# LTC6362_Schematic.net
KiCad netlist of a schematic drawn in Altium Designer
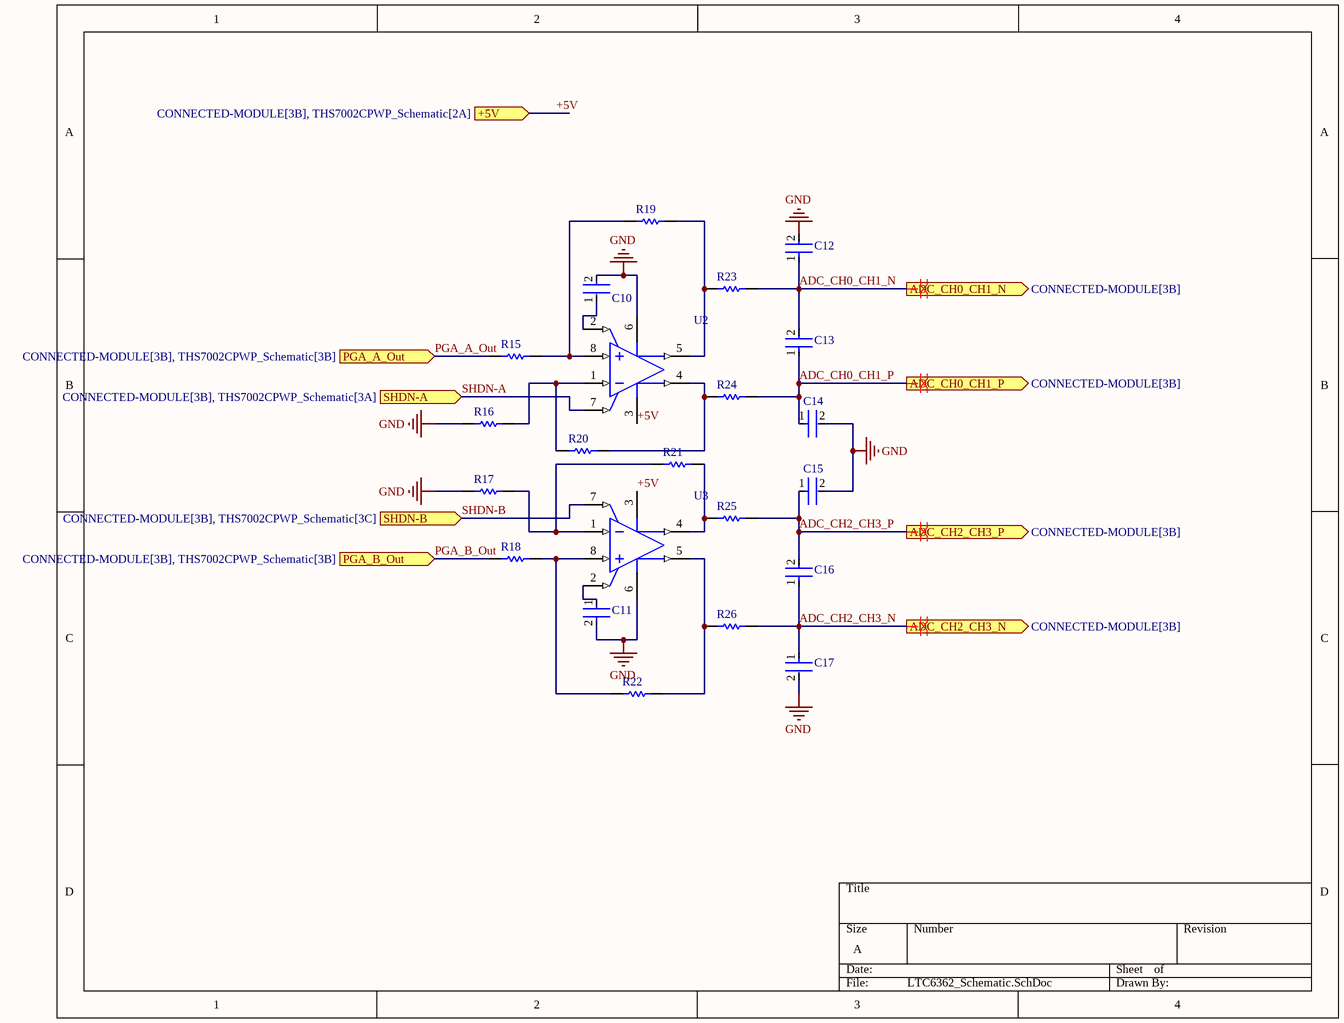
[diagram p0: LTC6362_Schematic.SchDoc]

(export (version "E")
  (design (tool "Eeschema 10.0.6"))
  (components
    (comp (ref "C10")
      (value "GRM155R71C104KA88D")
      (footprint "FP-GRM15-MFG")
      (description "CAP CER 0.1UF 16V X7R 0402")
      (fields
        (field (name "TOLERANCE") "10%")
        (field (name "OCTOPART") "https://octopart.com/grm155r71c104ka88d-murata-196880")
      )
      (libsource (lib "Altium Content Vault") (part "236180d848d6139a670b325ea6854c9"))
    )
    (comp (ref "C11")
      (value "GRM155R71C104KA88D")
      (footprint "FP-GRM15-MFG")
      (description "CAP CER 0.1UF 16V X7R 0402")
      (fields
        (field (name "TOLERANCE") "10%")
        (field (name "OCTOPART") "https://octopart.com/grm155r71c104ka88d-murata-196880")
      )
      (libsource (lib "Altium Content Vault") (part "236180d848d6139a670b325ea6854c9"))
    )
    (comp (ref "C12")
      (value "C0402C392K3RACTU")
      (footprint "FP-C0402-BB-MFG")
      (description "CAP CER 3900PF 25V X7R 0402")
      (fields
        (field (name "MANUFACTURER") "Kemet")
        (field (name "OCTOPART") "https://octopart.com/c0402c392k3ractu-kemet-141288")
      )
      (libsource (lib "Altium Content Vault") (part "b4654b650e69147ec39a6b967a45e02"))
    )
    (comp (ref "C13")
      (value "C0402C392K3RACTU")
      (footprint "FP-C0402-BB-MFG")
      (description "CAP CER 3900PF 25V X7R 0402")
      (fields
        (field (name "MANUFACTURER") "Kemet")
        (field (name "OCTOPART") "https://octopart.com/c0402c392k3ractu-kemet-141288")
      )
      (libsource (lib "Altium Content Vault") (part "b4654b650e69147ec39a6b967a45e02"))
    )
    (comp (ref "C14")
      (value "C0402C392K3RACTU")
      (footprint "FP-C0402-BB-MFG")
      (description "CAP CER 3900PF 25V X7R 0402")
      (fields
        (field (name "MANUFACTURER") "Kemet")
        (field (name "OCTOPART") "https://octopart.com/c0402c392k3ractu-kemet-141288")
      )
      (libsource (lib "Altium Content Vault") (part "b4654b650e69147ec39a6b967a45e02"))
    )
    (comp (ref "C15")
      (value "C0402C392K3RACTU")
      (footprint "FP-C0402-BB-MFG")
      (description "CAP CER 3900PF 25V X7R 0402")
      (fields
        (field (name "MANUFACTURER") "Kemet")
        (field (name "OCTOPART") "https://octopart.com/c0402c392k3ractu-kemet-141288")
      )
      (libsource (lib "Altium Content Vault") (part "b4654b650e69147ec39a6b967a45e02"))
    )
    (comp (ref "C16")
      (value "C0402C392K3RACTU")
      (footprint "FP-C0402-BB-MFG")
      (description "CAP CER 3900PF 25V X7R 0402")
      (fields
        (field (name "MANUFACTURER") "Kemet")
        (field (name "OCTOPART") "https://octopart.com/c0402c392k3ractu-kemet-141288")
      )
      (libsource (lib "Altium Content Vault") (part "b4654b650e69147ec39a6b967a45e02"))
    )
    (comp (ref "C17")
      (value "C0402C392K3RACTU")
      (footprint "FP-C0402-BB-MFG")
      (description "CAP CER 3900PF 25V X7R 0402")
      (fields
        (field (name "MANUFACTURER") "Kemet")
        (field (name "OCTOPART") "https://octopart.com/c0402c392k3ractu-kemet-141288")
      )
      (libsource (lib "Altium Content Vault") (part "b4654b650e69147ec39a6b967a45e02"))
    )
    (comp (ref "R15")
      (value "ERJ-2RKF1241X")
      (footprint "RESC1005X40X25ML05T05")
      (fields (field (name "MANUFACTURER") "Panasonic"))
      (libsource (lib "Altium Content Vault") (part "RES"))
    )
    (comp (ref "R16")
      (value "ERJ-2RKF1241X")
      (footprint "RESC1005X40X25ML05T05")
      (fields (field (name "MANUFACTURER") "Panasonic"))
      (libsource (lib "Altium Content Vault") (part "RES"))
    )
    (comp (ref "R17")
      (value "ERJ-2RKF1241X")
      (footprint "RESC1005X40X25ML05T05")
      (fields (field (name "MANUFACTURER") "Panasonic"))
      (libsource (lib "Altium Content Vault") (part "RES"))
    )
    (comp (ref "R18")
      (value "ERJ-2RKF1241X")
      (footprint "RESC1005X40X25ML05T05")
      (fields (field (name "MANUFACTURER") "Panasonic"))
      (libsource (lib "Altium Content Vault") (part "RES"))
    )
    (comp (ref "R19")
      (value "ERJ-2RKF1001X")
      (footprint "RESC1005X40X25NL05T05")
      (description "Chip Resistor, 1 KOhm, +/- 1%, 100 mW, -55 to 155 degC, 0402 (1005 Metric), RoHS, Tape and Reel")
      (fields (field (name "MANUFACTURER") "Basic Passives") (field (name "TOLERANCE") "1%"))
      (libsource (lib "Altium Content Vault") (part "RES-2"))
    )
    (comp (ref "R20")
      (value "ERJ-2RKF1001X")
      (footprint "RESC1005X40X25NL05T05")
      (description "Chip Resistor, 1 KOhm, +/- 1%, 100 mW, -55 to 155 degC, 0402 (1005 Metric), RoHS, Tape and Reel")
      (fields (field (name "MANUFACTURER") "Basic Passives") (field (name "TOLERANCE") "1%"))
      (libsource (lib "Altium Content Vault") (part "RES-2"))
    )
    (comp (ref "R21")
      (value "ERJ-2RKF1001X")
      (footprint "RESC1005X40X25NL05T05")
      (description "Chip Resistor, 1 KOhm, +/- 1%, 100 mW, -55 to 155 degC, 0402 (1005 Metric), RoHS, Tape and Reel")
      (fields (field (name "MANUFACTURER") "Basic Passives") (field (name "TOLERANCE") "1%"))
      (libsource (lib "Altium Content Vault") (part "RES-2"))
    )
    (comp (ref "R22")
      (value "ERJ-2RKF1001X")
      (footprint "RESC1005X40X25NL05T05")
      (description "Chip Resistor, 1 KOhm, +/- 1%, 100 mW, -55 to 155 degC, 0402 (1005 Metric), RoHS, Tape and Reel")
      (fields (field (name "MANUFACTURER") "Basic Passives") (field (name "TOLERANCE") "1%"))
      (libsource (lib "Altium Content Vault") (part "RES-2"))
    )
    (comp (ref "R23")
      (value "RC0402FR-0735R7L")
      (footprint "RESC1005X40X25ML05T10")
      (fields (field (name "MANUFACTURER") "Yageo"))
      (libsource (lib "Altium Content Vault") (part "RES"))
    )
    (comp (ref "R24")
      (value "RC0402FR-0735R7L")
      (footprint "RESC1005X40X25ML05T10")
      (fields (field (name "MANUFACTURER") "Yageo"))
      (libsource (lib "Altium Content Vault") (part "RES"))
    )
    (comp (ref "R25")
      (value "RC0402FR-0735R7L")
      (footprint "RESC1005X40X25ML05T10")
      (fields (field (name "MANUFACTURER") "Yageo"))
      (libsource (lib "Altium Content Vault") (part "RES"))
    )
    (comp (ref "R26")
      (value "RC0402FR-0735R7L")
      (footprint "RESC1005X40X25ML05T10")
      (fields (field (name "MANUFACTURER") "Yageo"))
      (libsource (lib "Altium Content Vault") (part "RES"))
    )
    (comp (ref "U2")
      (value "LTC6362HMS8#PBF")
      (footprint "LT-MS8-8_L")
      (fields
        (field (name "LINEAR TECHNOLOGY PART NUMBER") "LTC6362")
        (field (name "MANUFACTURER") "Linear Technology")
      )
      (libsource (lib "LTC6362HMS_Schematic") (part "CMP-0359-00920-2"))
    )
    (comp (ref "U3")
      (value "LTC6362HMS8#PBF")
      (footprint "LT-MS8-8_L")
      (fields
        (field (name "LINEAR TECHNOLOGY PART NUMBER") "LTC6362")
        (field (name "MANUFACTURER") "Linear Technology")
      )
      (libsource (lib "LTC6362HMS_Schematic") (part "CMP-0359-00920-2"))
    )
  )
  (nets
    (net (code "1") (name "/+5V") (class "Default")
      (node (ref "U2") (pin "3") (pinfunction "V+_3") (pintype "power_in"))
      (node (ref "U3") (pin "3") (pinfunction "V+_3") (pintype "power_in"))
    )
    (net (code "2") (name "/ADC_CH0_CH1_N") (class "Default")
      (node (ref "C12") (pin "1") (pinfunction "1_1") (pintype "passive"))
      (node (ref "C13") (pin "2") (pinfunction "2_2") (pintype "passive"))
      (node (ref "R23") (pin "2") (pinfunction "2_2") (pintype "passive"))
    )
    (net (code "3") (name "/ADC_CH0_CH1_P") (class "Default")
      (node (ref "C13") (pin "1") (pinfunction "1_1") (pintype "passive"))
      (node (ref "C14") (pin "1") (pinfunction "1_1") (pintype "passive"))
      (node (ref "R24") (pin "2") (pinfunction "2_2") (pintype "passive"))
    )
    (net (code "4") (name "/ADC_CH2_CH3_N") (class "Default")
      (node (ref "C16") (pin "1") (pinfunction "1_1") (pintype "passive"))
      (node (ref "C17") (pin "1") (pinfunction "1_1") (pintype "passive"))
      (node (ref "R26") (pin "2") (pinfunction "2_2") (pintype "passive"))
    )
    (net (code "5") (name "/ADC_CH2_CH3_P") (class "Default")
      (node (ref "C15") (pin "1") (pinfunction "1_1") (pintype "passive"))
      (node (ref "C16") (pin "2") (pinfunction "2_2") (pintype "passive"))
      (node (ref "R25") (pin "2") (pinfunction "2_2") (pintype "passive"))
    )
    (net (code "6") (name "/PGA_A_Out") (class "Default")
      (node (ref "R15") (pin "1") (pinfunction "1_1") (pintype "passive"))
    )
    (net (code "7") (name "/PGA_B_Out") (class "Default")
      (node (ref "R18") (pin "1") (pinfunction "1_1") (pintype "passive"))
    )
    (net (code "8") (name "/SHDN-A") (class "Default")
      (node (ref "U2") (pin "7") (pinfunction "~{SHDN}_7") (pintype "input"))
    )
    (net (code "9") (name "/SHDN-B") (class "Default")
      (node (ref "U3") (pin "7") (pinfunction "~{SHDN}_7") (pintype "input"))
    )
    (net (code "10") (name "GND") (class "Default")
      (node (ref "C10") (pin "2") (pinfunction "2_2") (pintype "passive"))
      (node (ref "C11") (pin "2") (pinfunction "2_2") (pintype "passive"))
      (node (ref "C12") (pin "2") (pinfunction "2_2") (pintype "passive"))
      (node (ref "C14") (pin "2") (pinfunction "2_2") (pintype "passive"))
      (node (ref "C15") (pin "2") (pinfunction "2_2") (pintype "passive"))
      (node (ref "C17") (pin "2") (pinfunction "2_2") (pintype "passive"))
      (node (ref "R16") (pin "1") (pinfunction "1_1") (pintype "passive"))
      (node (ref "R17") (pin "1") (pinfunction "1_1") (pintype "passive"))
      (node (ref "U2") (pin "6") (pinfunction "V-_6") (pintype "power_in"))
      (node (ref "U3") (pin "6") (pinfunction "V-_6") (pintype "power_in"))
    )
    (net (code "11") (name "Net-(U2-+IN)") (class "Default")
      (node (ref "R15") (pin "2") (pinfunction "2_2") (pintype "passive"))
      (node (ref "R19") (pin "1") (pinfunction "1_1") (pintype "passive"))
      (node (ref "U2") (pin "8") (pinfunction "+IN_8") (pintype "input"))
    )
    (net (code "12") (name "Net-(U2-+OUT)") (class "Default")
      (node (ref "R20") (pin "2") (pinfunction "2_2") (pintype "passive"))
      (node (ref "R24") (pin "1") (pinfunction "1_1") (pintype "passive"))
      (node (ref "U2") (pin "4") (pinfunction "+OUT_4") (pintype "output"))
    )
    (net (code "13") (name "Net-(U2--IN)") (class "Default")
      (node (ref "R16") (pin "2") (pinfunction "2_2") (pintype "passive"))
      (node (ref "R20") (pin "1") (pinfunction "1_1") (pintype "passive"))
      (node (ref "U2") (pin "1") (pinfunction "-IN_1") (pintype "input"))
    )
    (net (code "14") (name "Net-(U2--OUT)") (class "Default")
      (node (ref "R19") (pin "2") (pinfunction "2_2") (pintype "passive"))
      (node (ref "R23") (pin "1") (pinfunction "1_1") (pintype "passive"))
      (node (ref "U2") (pin "5") (pinfunction "-OUT_5") (pintype "output"))
    )
    (net (code "15") (name "Net-(U2-VOCM)") (class "Default")
      (node (ref "C10") (pin "1") (pinfunction "1_1") (pintype "passive"))
      (node (ref "U2") (pin "2") (pinfunction "VOCM_2") (pintype "input"))
    )
    (net (code "16") (name "Net-(U3-+IN)") (class "Default")
      (node (ref "R18") (pin "2") (pinfunction "2_2") (pintype "passive"))
      (node (ref "R22") (pin "1") (pinfunction "1_1") (pintype "passive"))
      (node (ref "U3") (pin "8") (pinfunction "+IN_8") (pintype "input"))
    )
    (net (code "17") (name "Net-(U3-+OUT)") (class "Default")
      (node (ref "R21") (pin "2") (pinfunction "2_2") (pintype "passive"))
      (node (ref "R25") (pin "1") (pinfunction "1_1") (pintype "passive"))
      (node (ref "U3") (pin "4") (pinfunction "+OUT_4") (pintype "output"))
    )
    (net (code "18") (name "Net-(U3--IN)") (class "Default")
      (node (ref "R17") (pin "2") (pinfunction "2_2") (pintype "passive"))
      (node (ref "R21") (pin "1") (pinfunction "1_1") (pintype "passive"))
      (node (ref "U3") (pin "1") (pinfunction "-IN_1") (pintype "input"))
    )
    (net (code "19") (name "Net-(U3--OUT)") (class "Default")
      (node (ref "R22") (pin "2") (pinfunction "2_2") (pintype "passive"))
      (node (ref "R26") (pin "1") (pinfunction "1_1") (pintype "passive"))
      (node (ref "U3") (pin "5") (pinfunction "-OUT_5") (pintype "output"))
    )
    (net (code "20") (name "Net-(U3-VOCM)") (class "Default")
      (node (ref "C11") (pin "1") (pinfunction "1_1") (pintype "passive"))
      (node (ref "U3") (pin "2") (pinfunction "VOCM_2") (pintype "input"))
    )
  )
)
